# LED.net
KiCad netlist of a schematic drawn in EAGLE
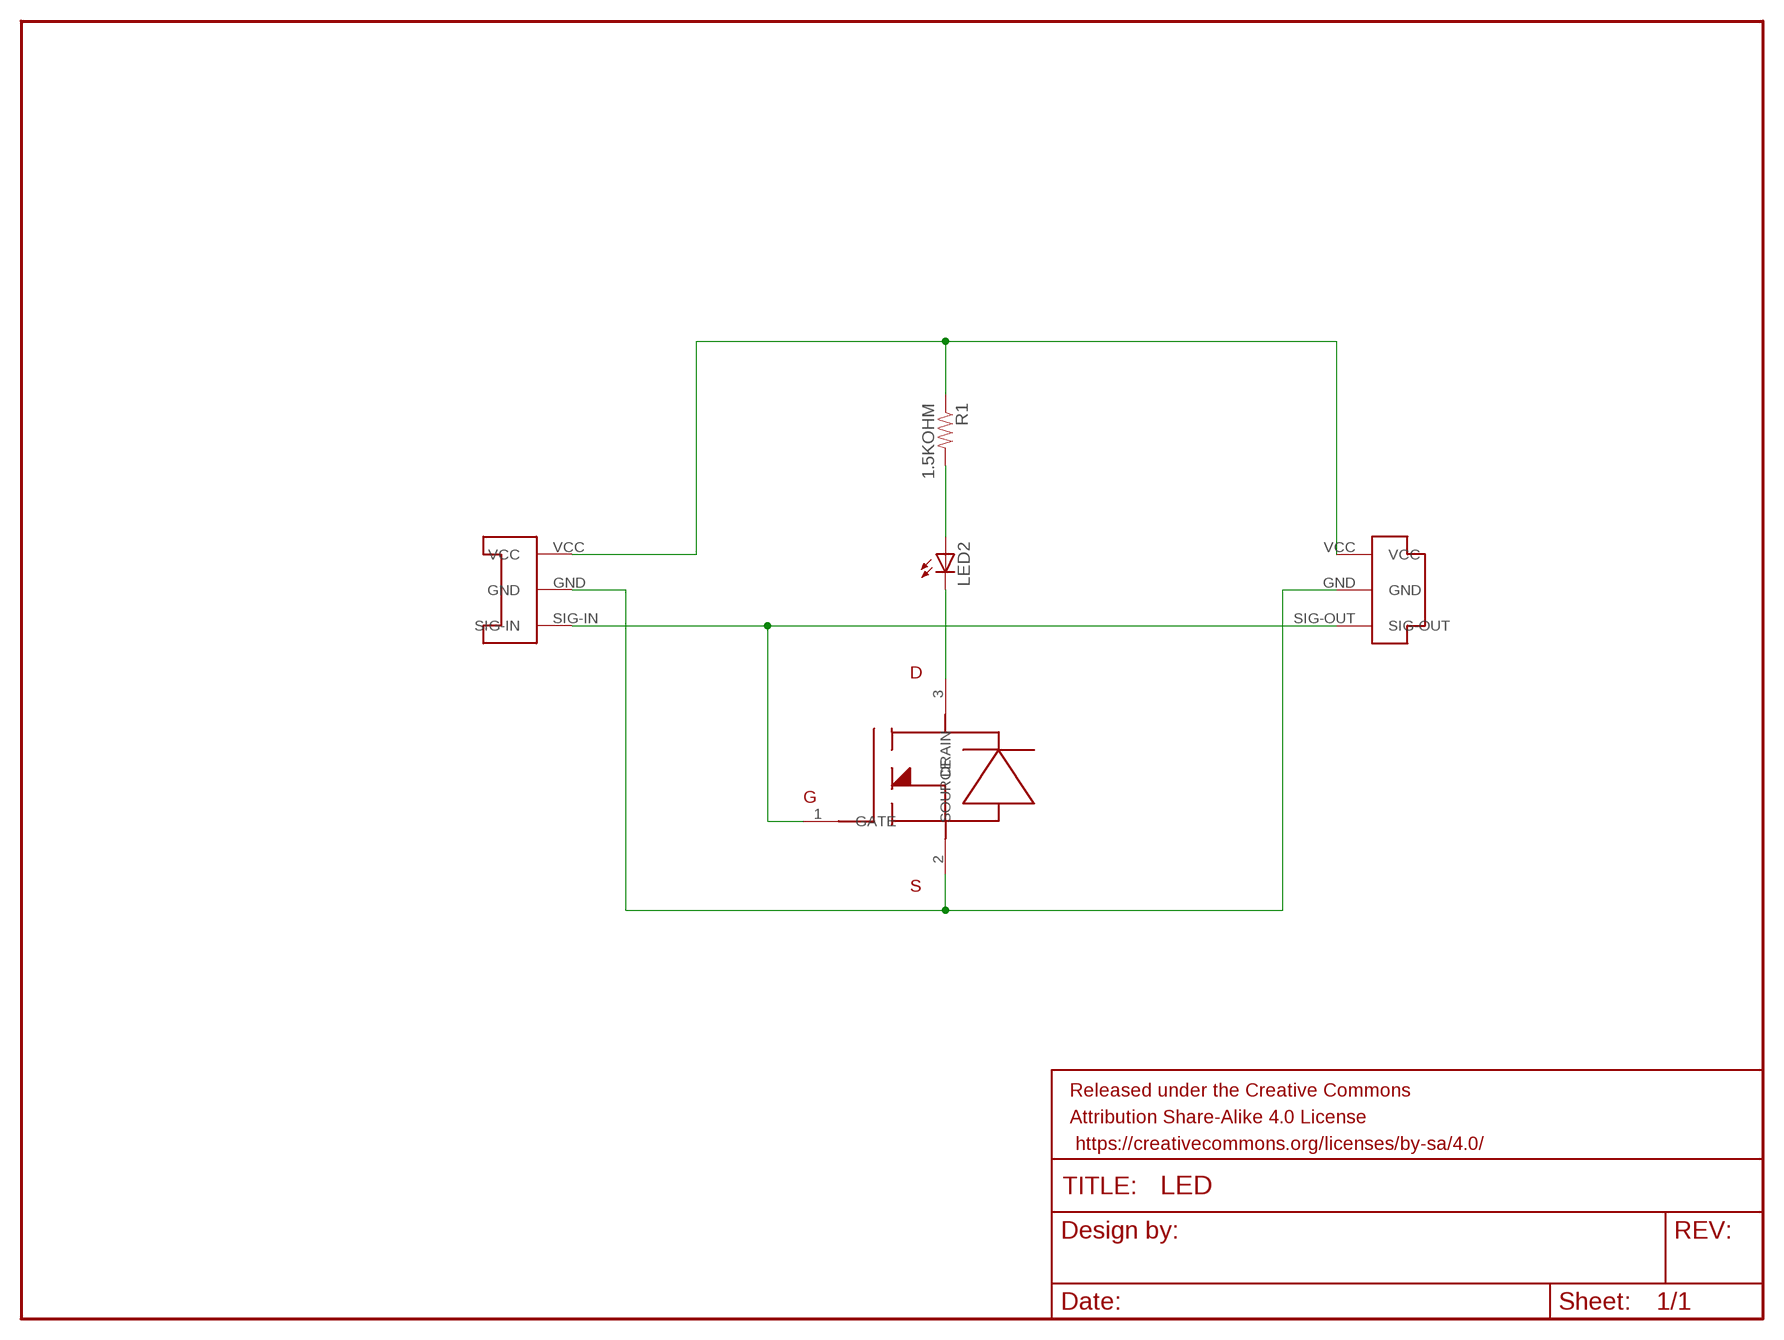
[diagram p0: schematic, sheet 1]

(export (version "E")
  (design (tool "Eeschema 10.0.6"))
  (components
    (comp (ref "FRAME1")
      (value "FRAME-LETTERNO_PACKAGE")
      (footprint "eagle-import:DUMMY")
      (fields (field (name "DESIGNER") "Nobody"))
      (libsource (lib "eagle-import") (part "FRAME-LETTERNO_PACKAGE"))
    )
    (comp (ref "LED2")
      (value "LEDCHIPLED_1206")
      (footprint "eagle-import:CHIPLED_1206")
      (libsource (lib "eagle-import") (part "LEDCHIPLED_1206"))
    )
    (comp (ref "R1")
      (value "1.5KOHM")
      (footprint "eagle-import:0603")
      (libsource (lib "eagle-import") (part "1.5KOHM-1/10W-1%(0603)"))
    )
    (comp (ref "U$1")
      (value "CONN-PLUG-3POS-3MM")
      (footprint "eagle-import:PLUG-3POS-3MM-SMD")
      (libsource (lib "eagle-import") (part "CONN-PLUG-3POS-3MM"))
    )
    (comp (ref "U$2")
      (value "CONN-SOCKET-3POS-3MM")
      (footprint "eagle-import:SOCKET-3POS-3MM-SMD")
      (libsource (lib "eagle-import") (part "CONN-SOCKET-3POS-3MM"))
    )
    (comp (ref "U$3")
      (value "MOSFET-N-CHAN")
      (footprint "eagle-import:SOT23-3")
      (libsource (lib "eagle-import") (part "MOSFET-N-CHAN"))
    )
  )
  (nets
    (net (code "1") (name "Net-(LED2-PadA)") (class "Default")
      (node (ref "LED2") (pin "A") (pinfunction "A_A") (pintype "passive"))
      (node (ref "R1") (pin "2") (pinfunction "2_2") (pintype "passive"))
    )
    (net (code "2") (name "Net-(R1-Pad1)") (class "Default")
      (node (ref "R1") (pin "1") (pinfunction "1_1") (pintype "passive"))
      (node (ref "U$1") (pin "VCC") (pinfunction "VCC_VCC") (pintype "power_in"))
      (node (ref "U$2") (pin "VCC") (pinfunction "VCC_VCC") (pintype "power_in"))
    )
    (net (code "3") (name "Net-(U$3-DRAIN)") (class "Default")
      (node (ref "LED2") (pin "C") (pinfunction "C_C") (pintype "passive"))
      (node (ref "U$3") (pin "3") (pinfunction "DRAIN_3") (pintype "passive"))
    )
    (net (code "4") (name "Net-(U$3-GATE)") (class "Default")
      (node (ref "U$1") (pin "SIG-OUT") (pinfunction "SIG-OUT_SIG-OUT") (pintype "bidirectional"))
      (node (ref "U$2") (pin "SIG-IN") (pinfunction "SIG-IN_SIG-IN") (pintype "bidirectional"))
      (node (ref "U$3") (pin "1") (pinfunction "GATE_1") (pintype "input"))
    )
    (net (code "5") (name "Net-(U$3-SOURCE)") (class "Default")
      (node (ref "U$1") (pin "GND") (pinfunction "GND_GND") (pintype "power_in"))
      (node (ref "U$2") (pin "GND") (pinfunction "GND_GND") (pintype "power_in"))
      (node (ref "U$3") (pin "2") (pinfunction "SOURCE_2") (pintype "passive"))
    )
  )
)
